# Adafruit_TS2012_TPA2012_Class_D_Audio_Am.net
KiCad netlist of a schematic drawn in EAGLE
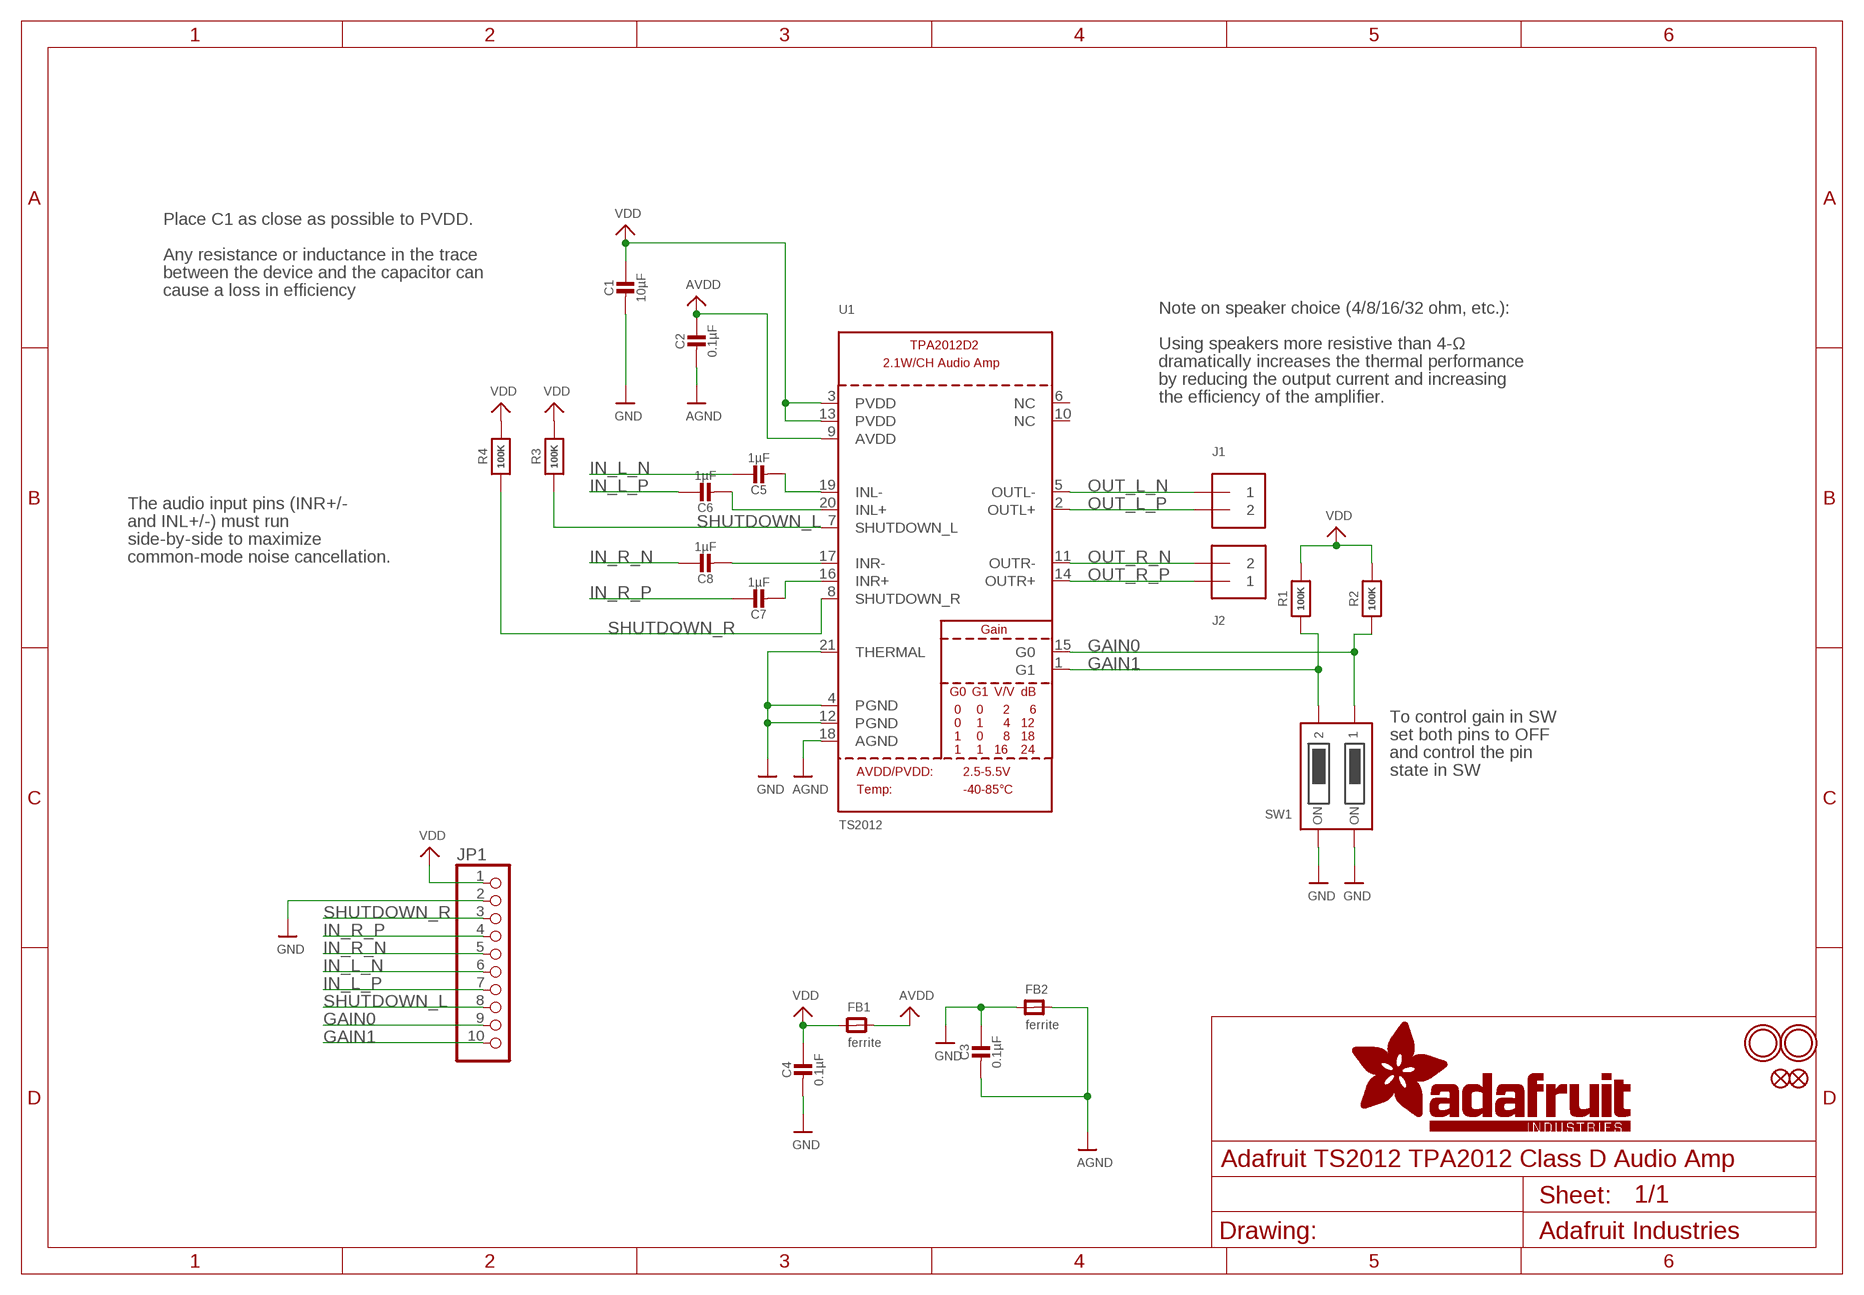
[diagram p0: schematic, sheet 1]

(export (version "E")
  (design (tool "Eeschema 10.0.6"))
  (components
    (comp (ref "C1")
      (value "10µF")
      (footprint "eagle-import:_0805MP")
      (libsource (lib "eagle-import") (part "CAP_CERAMIC_0805MP"))
    )
    (comp (ref "C2")
      (value "0.1µF")
      (footprint "eagle-import:_0805MP")
      (libsource (lib "eagle-import") (part "CAP_CERAMIC_0805MP"))
    )
    (comp (ref "C3")
      (value "0.1µF")
      (footprint "eagle-import:_0805MP")
      (libsource (lib "eagle-import") (part "CAP_CERAMIC_0805MP"))
    )
    (comp (ref "C4")
      (value "0.1µF")
      (footprint "eagle-import:_0805MP")
      (libsource (lib "eagle-import") (part "CAP_CERAMIC_0805MP"))
    )
    (comp (ref "C5")
      (value "1µF")
      (footprint "eagle-import:_0805MP")
      (libsource (lib "eagle-import") (part "CAP_CERAMIC_0805MP"))
    )
    (comp (ref "C6")
      (value "1µF")
      (footprint "eagle-import:_0805MP")
      (libsource (lib "eagle-import") (part "CAP_CERAMIC_0805MP"))
    )
    (comp (ref "C7")
      (value "1µF")
      (footprint "eagle-import:_0805MP")
      (libsource (lib "eagle-import") (part "CAP_CERAMIC_0805MP"))
    )
    (comp (ref "C8")
      (value "1µF")
      (footprint "eagle-import:_0805MP")
      (libsource (lib "eagle-import") (part "CAP_CERAMIC_0805MP"))
    )
    (comp (ref "FB1")
      (value "ferrite")
      (footprint "eagle-import:_0805MP")
      (libsource (lib "eagle-import") (part "FERRITE_0805MP"))
    )
    (comp (ref "FB2")
      (value "ferrite")
      (footprint "eagle-import:_0805MP")
      (libsource (lib "eagle-import") (part "FERRITE_0805MP"))
    )
    (comp (ref "FID1")
      (value "FIDUCIAL\"\"")
      (footprint "eagle-import:FIDUCIAL_1MM")
      (libsource (lib "eagle-import") (part "FIDUCIAL{dblquote}{dblquote}"))
    )
    (comp (ref "FID2")
      (value "FIDUCIAL\"\"")
      (footprint "eagle-import:FIDUCIAL_1MM")
      (libsource (lib "eagle-import") (part "FIDUCIAL{dblquote}{dblquote}"))
    )
    (comp (ref "J1")
      (value "TERMBLOCK_1X2")
      (footprint "eagle-import:TERMBLOCK_1X2-3.5MM")
      (libsource (lib "eagle-import") (part "TERMBLOCK_1X2"))
    )
    (comp (ref "J2")
      (value "TERMBLOCK_1X2")
      (footprint "eagle-import:TERMBLOCK_1X2-3.5MM")
      (libsource (lib "eagle-import") (part "TERMBLOCK_1X2"))
    )
    (comp (ref "JP1")
      (value "HEADER-1X1070MIL")
      (footprint "eagle-import:1X10_ROUND70")
      (libsource (lib "eagle-import") (part "HEADER-1X1070MIL"))
    )
    (comp (ref "R1")
      (value "100K")
      (footprint "eagle-import:_0805MP")
      (libsource (lib "eagle-import") (part "RESISTOR_0805MP"))
    )
    (comp (ref "R2")
      (value "100K")
      (footprint "eagle-import:_0805MP")
      (libsource (lib "eagle-import") (part "RESISTOR_0805MP"))
    )
    (comp (ref "R3")
      (value "100K")
      (footprint "eagle-import:_0805MP")
      (libsource (lib "eagle-import") (part "RESISTOR_0805MP"))
    )
    (comp (ref "R4")
      (value "100K")
      (footprint "eagle-import:_0805MP")
      (libsource (lib "eagle-import") (part "RESISTOR_0805MP"))
    )
    (comp (ref "SW1")
      (value "DIPSWITCH_2PIN")
      (footprint "eagle-import:DIPSWITCH_2PIN")
      (libsource (lib "eagle-import") (part "DIPSWITCH_2PIN"))
    )
    (comp (ref "U$20")
      (value "MOUNTINGHOLE2.5_THICK")
      (footprint "eagle-import:MOUNTINGHOLE_2.5_PLATED_THICK")
      (libsource (lib "eagle-import") (part "MOUNTINGHOLE2.5_THICK"))
    )
    (comp (ref "U$21")
      (value "MOUNTINGHOLE2.5_THICK")
      (footprint "eagle-import:MOUNTINGHOLE_2.5_PLATED_THICK")
      (libsource (lib "eagle-import") (part "MOUNTINGHOLE2.5_THICK"))
    )
    (comp (ref "U1")
      (value "TS2012")
      (footprint "eagle-import:WQFN20")
      (libsource (lib "eagle-import") (part "AUDIOAMP_TPA2012D2"))
    )
  )
  (nets
    (net (code "1") (name "/GAIN0") (class "Default")
      (node (ref "JP1") (pin "9") (pinfunction "9_9") (pintype "passive"))
      (node (ref "R2") (pin "1") (pinfunction "1_1") (pintype "passive"))
      (node (ref "SW1") (pin "1OFF") (pinfunction "1OFF_1OFF") (pintype "bidirectional"))
      (node (ref "U1") (pin "15") (pinfunction "G0_15") (pintype "input"))
    )
    (net (code "2") (name "/GAIN1") (class "Default")
      (node (ref "JP1") (pin "10") (pinfunction "10_10") (pintype "passive"))
      (node (ref "R1") (pin "1") (pinfunction "1_1") (pintype "passive"))
      (node (ref "SW1") (pin "2OFF") (pinfunction "2OFF_2OFF") (pintype "bidirectional"))
      (node (ref "U1") (pin "1") (pinfunction "G1_1") (pintype "input"))
    )
    (net (code "3") (name "/IN_L_N") (class "Default")
      (node (ref "C5") (pin "1") (pinfunction "1_1") (pintype "passive"))
      (node (ref "JP1") (pin "6") (pinfunction "6_6") (pintype "passive"))
    )
    (net (code "4") (name "/IN_L_P") (class "Default")
      (node (ref "C6") (pin "1") (pinfunction "1_1") (pintype "passive"))
      (node (ref "JP1") (pin "7") (pinfunction "7_7") (pintype "passive"))
    )
    (net (code "5") (name "/IN_R_N") (class "Default")
      (node (ref "C8") (pin "1") (pinfunction "1_1") (pintype "passive"))
      (node (ref "JP1") (pin "5") (pinfunction "5_5") (pintype "passive"))
    )
    (net (code "6") (name "/IN_R_P") (class "Default")
      (node (ref "C7") (pin "1") (pinfunction "1_1") (pintype "passive"))
      (node (ref "JP1") (pin "4") (pinfunction "4_4") (pintype "passive"))
    )
    (net (code "7") (name "/OUT_L_N") (class "Default")
      (node (ref "J1") (pin "1") (pinfunction "1_1") (pintype "passive"))
      (node (ref "U1") (pin "5") (pinfunction "OUTL-_5") (pintype "output"))
    )
    (net (code "8") (name "/OUT_L_P") (class "Default")
      (node (ref "J1") (pin "2") (pinfunction "2_2") (pintype "passive"))
      (node (ref "U1") (pin "2") (pinfunction "OUTL+_2") (pintype "output"))
    )
    (net (code "9") (name "/OUT_R_N") (class "Default")
      (node (ref "J2") (pin "2") (pinfunction "2_2") (pintype "passive"))
      (node (ref "U1") (pin "11") (pinfunction "OUTR-_11") (pintype "output"))
    )
    (net (code "10") (name "/OUT_R_P") (class "Default")
      (node (ref "J2") (pin "1") (pinfunction "1_1") (pintype "passive"))
      (node (ref "U1") (pin "14") (pinfunction "OUTR+_14") (pintype "output"))
    )
    (net (code "11") (name "/SHUTDOWN_L") (class "Default")
      (node (ref "JP1") (pin "8") (pinfunction "8_8") (pintype "passive"))
      (node (ref "R3") (pin "1") (pinfunction "1_1") (pintype "passive"))
      (node (ref "U1") (pin "7") (pinfunction "SHUTDOWN_L_7") (pintype "input"))
    )
    (net (code "12") (name "/SHUTDOWN_R") (class "Default")
      (node (ref "JP1") (pin "3") (pinfunction "3_3") (pintype "passive"))
      (node (ref "R4") (pin "1") (pinfunction "1_1") (pintype "passive"))
      (node (ref "U1") (pin "8") (pinfunction "SHUTDOWN_R_8") (pintype "input"))
    )
    (net (code "13") (name "AGND") (class "Default")
      (node (ref "C2") (pin "2") (pinfunction "2_2") (pintype "passive"))
      (node (ref "C3") (pin "2") (pinfunction "2_2") (pintype "passive"))
      (node (ref "FB2") (pin "2") (pinfunction "P$2_2") (pintype "passive"))
      (node (ref "U1") (pin "18") (pinfunction "AGND_18") (pintype "power_in"))
    )
    (net (code "14") (name "AVDD") (class "Default")
      (node (ref "C2") (pin "1") (pinfunction "1_1") (pintype "passive"))
      (node (ref "FB1") (pin "2") (pinfunction "P$2_2") (pintype "passive"))
      (node (ref "U1") (pin "9") (pinfunction "AVDD_9") (pintype "power_in"))
    )
    (net (code "15") (name "GND") (class "Default")
      (node (ref "C1") (pin "2") (pinfunction "2_2") (pintype "passive"))
      (node (ref "C3") (pin "1") (pinfunction "1_1") (pintype "passive"))
      (node (ref "C4") (pin "2") (pinfunction "2_2") (pintype "passive"))
      (node (ref "FB2") (pin "1") (pinfunction "P$1_1") (pintype "passive"))
      (node (ref "JP1") (pin "2") (pinfunction "2_2") (pintype "passive"))
      (node (ref "SW1") (pin "1ON") (pinfunction "1ON_1ON") (pintype "bidirectional"))
      (node (ref "SW1") (pin "2ON") (pinfunction "2ON_2ON") (pintype "bidirectional"))
      (node (ref "U1") (pin "12") (pinfunction "PGND_12") (pintype "power_in"))
      (node (ref "U1") (pin "21") (pinfunction "THERMAL_21") (pintype "bidirectional"))
      (node (ref "U1") (pin "4") (pinfunction "PGND_4") (pintype "power_in"))
    )
    (net (code "16") (name "Net-(U1-INL+)") (class "Default")
      (node (ref "C6") (pin "2") (pinfunction "2_2") (pintype "passive"))
      (node (ref "U1") (pin "20") (pinfunction "INL+_20") (pintype "input"))
    )
    (net (code "17") (name "Net-(U1-INL-)") (class "Default")
      (node (ref "C5") (pin "2") (pinfunction "2_2") (pintype "passive"))
      (node (ref "U1") (pin "19") (pinfunction "INL-_19") (pintype "input"))
    )
    (net (code "18") (name "Net-(U1-INR+)") (class "Default")
      (node (ref "C7") (pin "2") (pinfunction "2_2") (pintype "passive"))
      (node (ref "U1") (pin "16") (pinfunction "INR+_16") (pintype "input"))
    )
    (net (code "19") (name "Net-(U1-INR-)") (class "Default")
      (node (ref "C8") (pin "2") (pinfunction "2_2") (pintype "passive"))
      (node (ref "U1") (pin "17") (pinfunction "INR-_17") (pintype "input"))
    )
    (net (code "20") (name "VDD") (class "Default")
      (node (ref "C1") (pin "1") (pinfunction "1_1") (pintype "passive"))
      (node (ref "C4") (pin "1") (pinfunction "1_1") (pintype "passive"))
      (node (ref "FB1") (pin "1") (pinfunction "P$1_1") (pintype "passive"))
      (node (ref "JP1") (pin "1") (pinfunction "1_1") (pintype "passive"))
      (node (ref "R1") (pin "2") (pinfunction "2_2") (pintype "passive"))
      (node (ref "R2") (pin "2") (pinfunction "2_2") (pintype "passive"))
      (node (ref "R3") (pin "2") (pinfunction "2_2") (pintype "passive"))
      (node (ref "R4") (pin "2") (pinfunction "2_2") (pintype "passive"))
      (node (ref "U1") (pin "13") (pinfunction "PVDD_13") (pintype "power_in"))
      (node (ref "U1") (pin "3") (pinfunction "PVDD_3") (pintype "power_in"))
    )
    (net (code "21") (name "unconnected-(U1-NC-Pad6)") (class "Default")
      (node (ref "U1") (pin "6") (pinfunction "NC_6") (pintype "no_connect"))
    )
    (net (code "22") (name "unconnected-(U1-NC-Pad10)") (class "Default")
      (node (ref "U1") (pin "10") (pinfunction "NC_10") (pintype "no_connect"))
    )
  )
)
